# Arduino_MEGA2560_ref.net
KiCad netlist of a schematic drawn in EAGLE
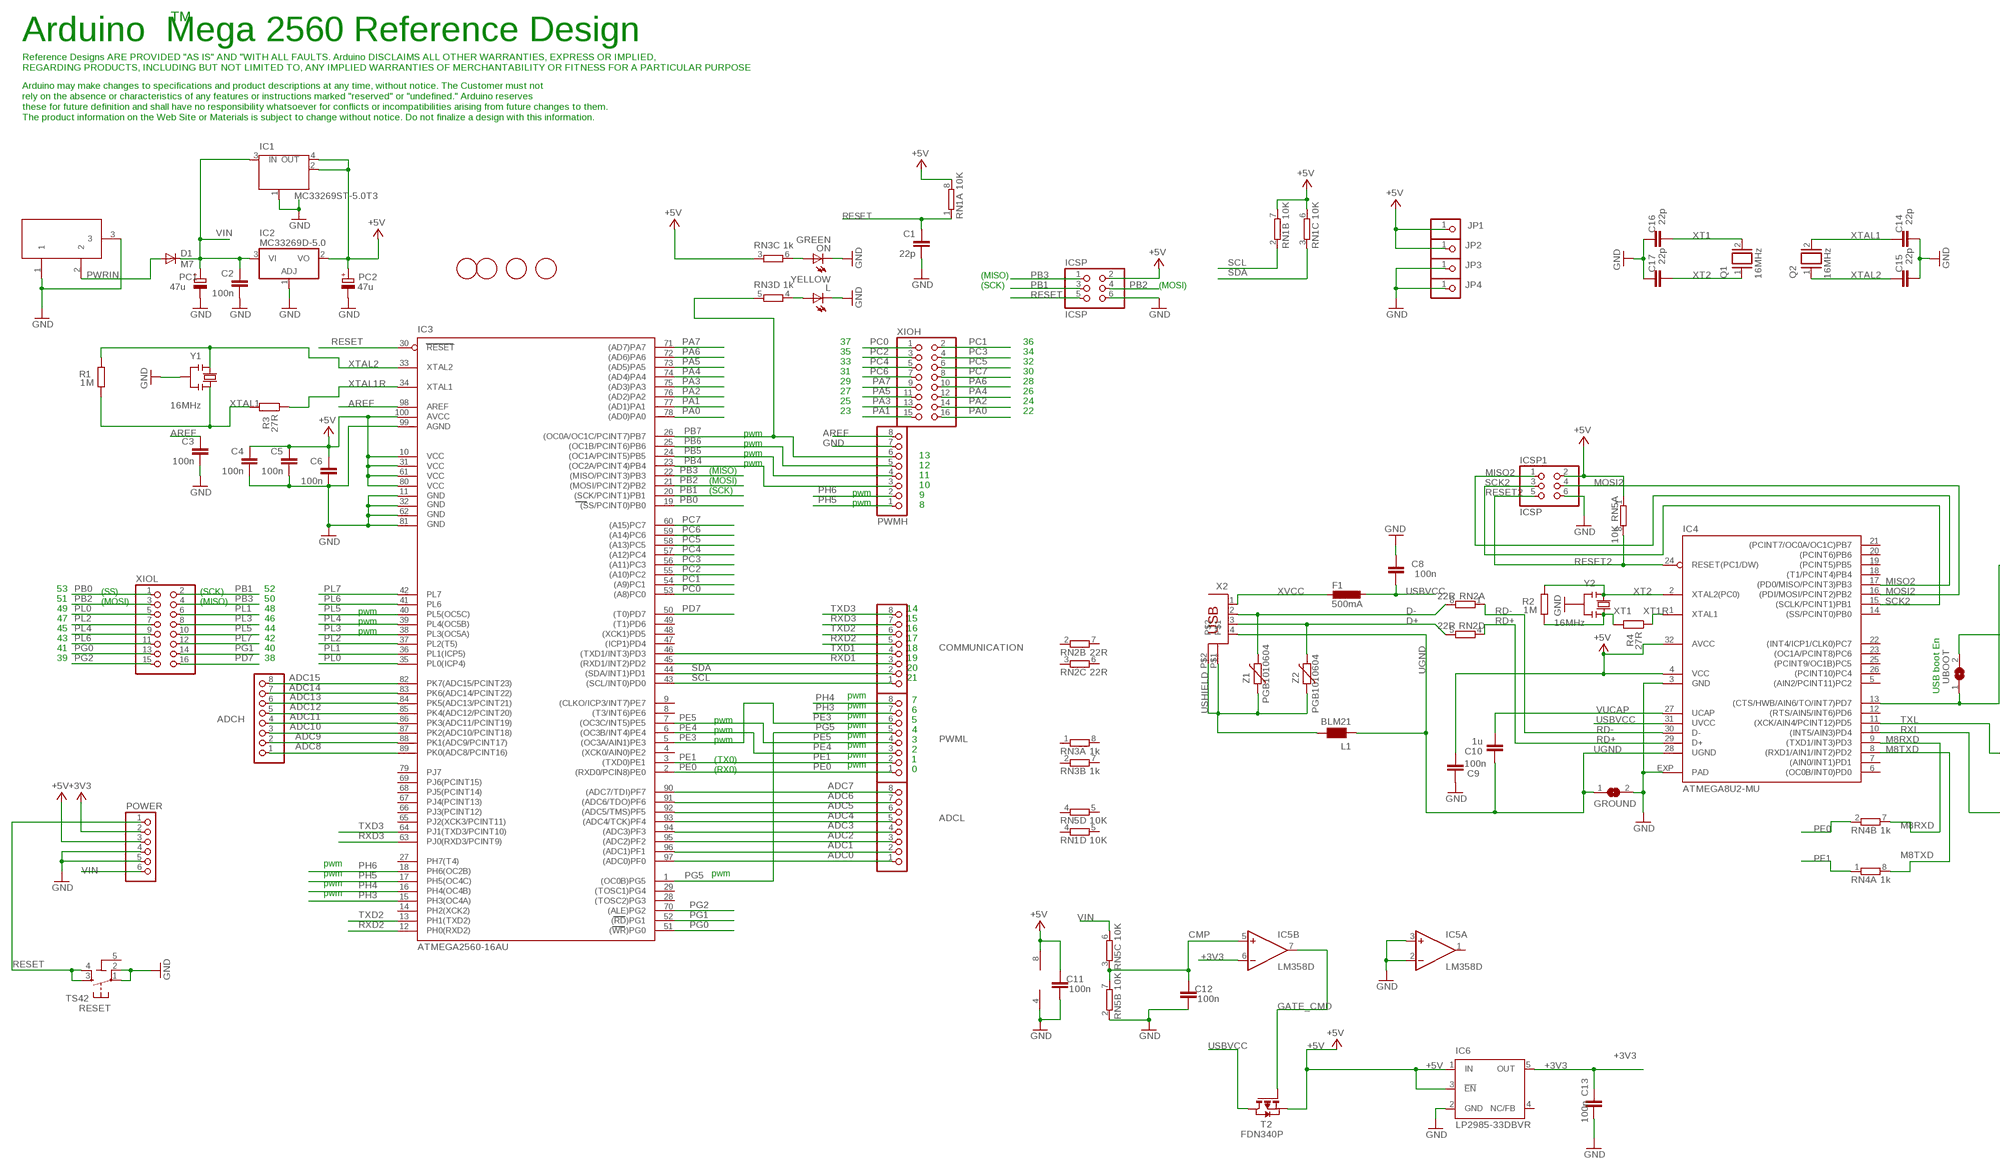
[diagram p0: schematic, sheet 1, part 1 of 2]
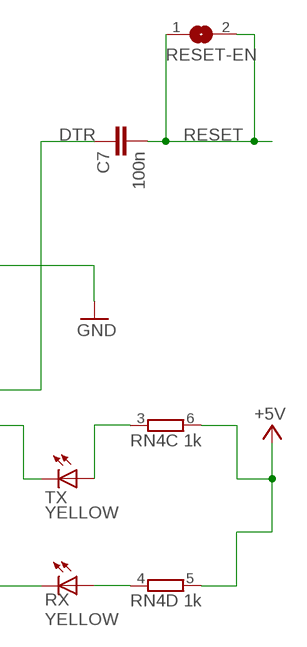
[diagram p1: schematic, sheet 1, part 2 of 2]

(export (version "E")
  (design (tool "Eeschema 10.0.6"))
  (components
    (comp (ref "ADCH")
      (value "PINHD-1X8")
      (footprint "eagle-import:1X08")
      (libsource (lib "eagle-import") (part "PINHD-1X8"))
    )
    (comp (ref "ADCL")
      (value "PINHD-1X8")
      (footprint "eagle-import:1X08")
      (libsource (lib "eagle-import") (part "PINHD-1X8"))
    )
    (comp (ref "C1")
      (value "22p")
      (footprint "eagle-import:C0603-ROUND")
      (libsource (lib "eagle-import") (part "C-EU0603-RND"))
    )
    (comp (ref "C2")
      (value "100n")
      (footprint "eagle-import:C0603-ROUND")
      (libsource (lib "eagle-import") (part "C-EU0603-RND"))
    )
    (comp (ref "C3")
      (value "100n")
      (footprint "eagle-import:C0603-ROUND")
      (libsource (lib "eagle-import") (part "C-EU0603-RND"))
    )
    (comp (ref "C4")
      (value "100n")
      (footprint "eagle-import:C0603-ROUND")
      (libsource (lib "eagle-import") (part "C-EU0603-RND"))
    )
    (comp (ref "C5")
      (value "100n")
      (footprint "eagle-import:C0603-ROUND")
      (libsource (lib "eagle-import") (part "C-EU0603-RND"))
    )
    (comp (ref "C6")
      (value "100n")
      (footprint "eagle-import:C0603-ROUND")
      (libsource (lib "eagle-import") (part "C-EU0603-RND"))
    )
    (comp (ref "C7")
      (value "100n")
      (footprint "eagle-import:C0603-ROUND")
      (libsource (lib "eagle-import") (part "C-EU0603-RND"))
    )
    (comp (ref "C8")
      (value "100n")
      (footprint "eagle-import:C0603")
      (libsource (lib "eagle-import") (part "rcl_C-EUC0603"))
    )
    (comp (ref "C9")
      (value "100n")
      (footprint "eagle-import:C0603-ROUND")
      (libsource (lib "eagle-import") (part "C-EU0603-RND"))
    )
    (comp (ref "C10")
      (value "1u")
      (footprint "eagle-import:C0603-ROUND")
      (libsource (lib "eagle-import") (part "C-EU0603-RND"))
    )
    (comp (ref "C11")
      (value "100n")
      (footprint "eagle-import:C0603")
      (libsource (lib "eagle-import") (part "rcl_C-EUC0603"))
    )
    (comp (ref "C12")
      (value "100n")
      (footprint "eagle-import:C0603-ROUND")
      (libsource (lib "eagle-import") (part "C-EU0603-RND"))
    )
    (comp (ref "C13")
      (value "100n")
      (footprint "eagle-import:C0603-ROUND")
      (libsource (lib "eagle-import") (part "C-EU0603-RND"))
    )
    (comp (ref "C14")
      (value "22p")
      (footprint "eagle-import:C0603-ROUND")
      (libsource (lib "eagle-import") (part "C-EU0603-RND"))
    )
    (comp (ref "C15")
      (value "22p")
      (footprint "eagle-import:C0603-ROUND")
      (libsource (lib "eagle-import") (part "C-EU0603-RND"))
    )
    (comp (ref "C16")
      (value "22p")
      (footprint "eagle-import:C0603-ROUND")
      (libsource (lib "eagle-import") (part "C-EU0603-RND"))
    )
    (comp (ref "C17")
      (value "22p")
      (footprint "eagle-import:C0603-ROUND")
      (libsource (lib "eagle-import") (part "C-EU0603-RND"))
    )
    (comp (ref "COMMUNICATION")
      (value "PINHD-1X8")
      (footprint "eagle-import:1X08")
      (libsource (lib "eagle-import") (part "PINHD-1X8"))
    )
    (comp (ref "D1")
      (value "M7")
      (footprint "eagle-import:SMB")
      (libsource (lib "eagle-import") (part "DIODE-SMB"))
    )
    (comp (ref "F1")
      (value "500mA")
      (footprint "eagle-import:L1812")
      (libsource (lib "eagle-import") (part "L-EUL1812"))
    )
    (comp (ref "GROUND")
      (value "SJ")
      (footprint "eagle-import:SJ")
      (libsource (lib "eagle-import") (part "SJ"))
    )
    (comp (ref "IC1")
      (value "MC33269ST-5.0T3")
      (footprint "eagle-import:SOT223")
      (libsource (lib "eagle-import") (part "MC33269ST-3.3T3"))
    )
    (comp (ref "IC2")
      (value "MC33269D-5.0")
      (footprint "eagle-import:DPACK")
      (libsource (lib "eagle-import") (part "MC33269?D-5.0"))
    )
    (comp (ref "IC3")
      (value "ATMEGA2560-16AU")
      (footprint "eagle-import:TQFP100")
      (libsource (lib "eagle-import") (part "ATMEGAAU1280-16"))
    )
    (comp (ref "IC4")
      (value "ATMEGA8U2-MU")
      (footprint "eagle-import:QFN32")
      (libsource (lib "eagle-import") (part "ATMEGA8U2-MU"))
    )
    (comp (ref "IC5")
      (value "LM358D")
      (footprint "eagle-import:SO08")
      (libsource (lib "eagle-import") (part "LM358D"))
    )
    (comp (ref "IC6")
      (value "LP2985-33DBVR")
      (footprint "eagle-import:SOT23-DBV")
      (libsource (lib "eagle-import") (part "TPS77033"))
    )
    (comp (ref "ICSP")
      (value "ICSP")
      (footprint "eagle-import:2X03")
      (libsource (lib "eagle-import") (part "PINHD-2X3"))
    )
    (comp (ref "ICSP1")
      (value "ICSP")
      (footprint "eagle-import:2X03")
      (libsource (lib "eagle-import") (part "PINHD-2X3"))
    )
    (comp (ref "JP1")
      (value "PINHD-1X1")
      (footprint "eagle-import:1X01")
      (libsource (lib "eagle-import") (part "PINHD-1X1"))
    )
    (comp (ref "JP2")
      (value "PINHD-1X1")
      (footprint "eagle-import:1X01")
      (libsource (lib "eagle-import") (part "PINHD-1X1"))
    )
    (comp (ref "JP3")
      (value "PINHD-1X1")
      (footprint "eagle-import:1X01")
      (libsource (lib "eagle-import") (part "PINHD-1X1"))
    )
    (comp (ref "JP4")
      (value "PINHD-1X1")
      (footprint "eagle-import:1X01")
      (libsource (lib "eagle-import") (part "PINHD-1X1"))
    )
    (comp (ref "L")
      (value "YELLOW")
      (footprint "eagle-import:CHIP-LED0805")
      (libsource (lib "eagle-import") (part "LEDCHIP-LED0805"))
    )
    (comp (ref "L1")
      (value "BLM21")
      (footprint "eagle-import:0805")
      (libsource (lib "eagle-import") (part "WE-CBF_0805"))
    )
    (comp (ref "ON")
      (value "GREEN")
      (footprint "eagle-import:CHIP-LED0805")
      (libsource (lib "eagle-import") (part "LEDCHIP-LED0805"))
    )
    (comp (ref "PC1")
      (value "47u")
      (footprint "eagle-import:PANASONIC_D")
      (libsource (lib "eagle-import") (part "CPOL-EUD"))
    )
    (comp (ref "PC2")
      (value "47u")
      (footprint "eagle-import:PANASONIC_D")
      (libsource (lib "eagle-import") (part "CPOL-EUD"))
    )
    (comp (ref "POWER")
      (value "PINHD-1X6")
      (footprint "eagle-import:1X06")
      (libsource (lib "eagle-import") (part "PINHD-1X6"))
    )
    (comp (ref "PWMH")
      (value "PINHD-1X8")
      (footprint "eagle-import:1X08")
      (libsource (lib "eagle-import") (part "PINHD-1X8"))
    )
    (comp (ref "PWML")
      (value "PINHD-1X8")
      (footprint "eagle-import:1X08")
      (libsource (lib "eagle-import") (part "PINHD-1X8"))
    )
    (comp (ref "Q1")
      (value "16MHz")
      (footprint "eagle-import:QS")
      (libsource (lib "eagle-import") (part "XTAL/S"))
    )
    (comp (ref "Q2")
      (value "16MHz")
      (footprint "eagle-import:QS")
      (libsource (lib "eagle-import") (part "XTAL/S"))
    )
    (comp (ref "R1")
      (value "1M")
      (footprint "eagle-import:R0603-ROUND")
      (libsource (lib "eagle-import") (part "R-EU_R0603"))
    )
    (comp (ref "R2")
      (value "1M")
      (footprint "eagle-import:R0603-ROUND")
      (libsource (lib "eagle-import") (part "R-EU_R0603"))
    )
    (comp (ref "R3")
      (value "27R")
      (footprint "eagle-import:R0603-ROUND")
      (libsource (lib "eagle-import") (part "R-EU_R0603"))
    )
    (comp (ref "R4")
      (value "27R")
      (footprint "eagle-import:R0603-ROUND")
      (libsource (lib "eagle-import") (part "R-EU_R0603"))
    )
    (comp (ref "RESET")
      (value "TS42")
      (footprint "eagle-import:TS42")
      (libsource (lib "eagle-import") (part "TS42"))
    )
    (comp (ref "RESET-EN")
      (value "SJ")
      (footprint "eagle-import:SJ")
      (libsource (lib "eagle-import") (part "SJ"))
    )
    (comp (ref "RN1")
      (value "10K")
      (footprint "eagle-import:CAT16")
      (libsource (lib "eagle-import") (part "4R-NCAT16"))
    )
    (comp (ref "RN2")
      (value "22R")
      (footprint "eagle-import:CAY16")
      (libsource (lib "eagle-import") (part "4R-NCAY16"))
    )
    (comp (ref "RN3")
      (value "1k")
      (footprint "eagle-import:CAY16")
      (libsource (lib "eagle-import") (part "4R-NCAY16"))
    )
    (comp (ref "RN4")
      (value "1k")
      (footprint "eagle-import:CAY16")
      (libsource (lib "eagle-import") (part "4R-NCAY16"))
    )
    (comp (ref "RN5")
      (value "10K")
      (footprint "eagle-import:CAT16")
      (libsource (lib "eagle-import") (part "4R-NCAT16"))
    )
    (comp (ref "RX")
      (value "YELLOW")
      (footprint "eagle-import:CHIP-LED0805")
      (libsource (lib "eagle-import") (part "LEDCHIP-LED0805"))
    )
    (comp (ref "T2")
      (value "FDN340P")
      (footprint "eagle-import:SOT-23")
      (libsource (lib "eagle-import") (part "PMOSSOT23"))
    )
    (comp (ref "TX")
      (value "YELLOW")
      (footprint "eagle-import:CHIP-LED0805")
      (libsource (lib "eagle-import") (part "LEDCHIP-LED0805"))
    )
    (comp (ref "U$2")
      (value "FIDUCIALMOUNT")
      (footprint "eagle-import:FIDUCIA-MOUNT")
      (libsource (lib "eagle-import") (part "FIDUCIALMOUNT"))
    )
    (comp (ref "U$3")
      (value "FIDUCIALMOUNT")
      (footprint "eagle-import:FIDUCIA-MOUNT")
      (libsource (lib "eagle-import") (part "FIDUCIALMOUNT"))
    )
    (comp (ref "U$4")
      (value "FIDUCIALMOUNT")
      (footprint "eagle-import:FIDUCIA-MOUNT")
      (libsource (lib "eagle-import") (part "FIDUCIALMOUNT"))
    )
    (comp (ref "U$5")
      (value "FIDUCIALMOUNT")
      (footprint "eagle-import:FIDUCIA-MOUNT")
      (libsource (lib "eagle-import") (part "FIDUCIALMOUNT"))
    )
    (comp (ref "UBOOT")
      (value "SJ")
      (footprint "eagle-import:SJ")
      (libsource (lib "eagle-import") (part "SJ"))
    )
    (comp (ref "X1")
      (value "DC21MMX")
      (footprint "eagle-import:DC-21MM")
      (libsource (lib "eagle-import") (part "DC21MMX"))
    )
    (comp (ref "X2")
      (value "PN61729")
      (footprint "eagle-import:PN61729")
      (libsource (lib "eagle-import") (part "PN61729"))
    )
    (comp (ref "XIOH")
      (value "PINHD-2X8")
      (footprint "eagle-import:2X08")
      (libsource (lib "eagle-import") (part "PINHD-2X8"))
    )
    (comp (ref "XIOL")
      (value "PINHD-2X8")
      (footprint "eagle-import:2X08")
      (libsource (lib "eagle-import") (part "PINHD-2X8"))
    )
    (comp (ref "Y1")
      (value "16MHz")
      (footprint "eagle-import:RESONATOR")
      (libsource (lib "eagle-import") (part "RESONATORMU"))
    )
    (comp (ref "Y2")
      (value "16MHz")
      (footprint "eagle-import:RESONATOR")
      (libsource (lib "eagle-import") (part "RESONATORMU"))
    )
    (comp (ref "Z1")
      (value "PGB1010604")
      (footprint "eagle-import:CT_CN0603")
      (libsource (lib "eagle-import") (part "VARISTORCN0603"))
    )
    (comp (ref "Z2")
      (value "PGB1010604")
      (footprint "eagle-import:CT_CN0603")
      (libsource (lib "eagle-import") (part "VARISTORCN0603"))
    )
  )
  (nets
    (net (code "1") (name "+3V3") (class "Default")
      (node (ref "C13") (pin "2") (pinfunction "2_2") (pintype "passive"))
      (node (ref "IC5") (pin "6") (pinfunction "-IN_6") (pintype "input"))
      (node (ref "IC6") (pin "5") (pinfunction "OUT_5") (pintype "passive"))
      (node (ref "POWER") (pin "2") (pinfunction "2_2") (pintype "passive"))
    )
    (net (code "2") (name "+5V") (class "Default")
      (node (ref "C11") (pin "2") (pinfunction "2_2") (pintype "passive"))
      (node (ref "C4") (pin "1") (pinfunction "1_1") (pintype "passive"))
      (node (ref "C5") (pin "1") (pinfunction "1_1") (pintype "passive"))
      (node (ref "C6") (pin "1") (pinfunction "1_1") (pintype "passive"))
      (node (ref "C9") (pin "1") (pinfunction "1_1") (pintype "passive"))
      (node (ref "IC1") (pin "2") (pinfunction "OUT_2") (pintype "passive"))
      (node (ref "IC1") (pin "4") (pinfunction "OUT_4") (pintype "passive"))
      (node (ref "IC2") (pin "2") (pinfunction "VO_2") (pintype "passive"))
      (node (ref "IC3") (pin "10") (pinfunction "VCC_10") (pintype "power_in"))
      (node (ref "IC3") (pin "100") (pinfunction "AVCC_100") (pintype "power_in"))
      (node (ref "IC3") (pin "31") (pinfunction "VCC1_31") (pintype "power_in"))
      (node (ref "IC3") (pin "61") (pinfunction "VCC2_61") (pintype "power_in"))
      (node (ref "IC3") (pin "80") (pinfunction "VCC3_80") (pintype "power_in"))
      (node (ref "IC4") (pin "32") (pinfunction "AVCC_32") (pintype "power_in"))
      (node (ref "IC4") (pin "4") (pinfunction "VCC_4") (pintype "power_in"))
      (node (ref "IC5") (pin "8") (pinfunction "V+_8") (pintype "power_in"))
      (node (ref "IC6") (pin "1") (pinfunction "IN_1") (pintype "input"))
      (node (ref "IC6") (pin "3") (pinfunction "~{EN}_3") (pintype "input"))
      (node (ref "ICSP") (pin "2") (pinfunction "2_2") (pintype "passive"))
      (node (ref "ICSP1") (pin "2") (pinfunction "2_2") (pintype "passive"))
      (node (ref "JP1") (pin "1") (pinfunction "1_1") (pintype "passive"))
      (node (ref "JP2") (pin "1") (pinfunction "1_1") (pintype "passive"))
      (node (ref "PC2") (pin "+") (pinfunction "+_+") (pintype "passive"))
      (node (ref "POWER") (pin "3") (pinfunction "3_3") (pintype "passive"))
      (node (ref "RN1") (pin "6") (pinfunction "2_6") (pintype "passive"))
      (node (ref "RN1") (pin "7") (pinfunction "2_7") (pintype "passive"))
      (node (ref "RN1") (pin "8") (pinfunction "2_8") (pintype "passive"))
      (node (ref "RN3") (pin "3") (pinfunction "1_3") (pintype "passive"))
      (node (ref "RN4") (pin "5") (pinfunction "2_5") (pintype "passive"))
      (node (ref "RN4") (pin "6") (pinfunction "2_6") (pintype "passive"))
      (node (ref "RN5") (pin "1") (pinfunction "1_1") (pintype "passive"))
      (node (ref "T2") (pin "2") (pinfunction "S_2") (pintype "passive"))
    )
    (net (code "3") (name "/5-GND") (class "Default")
      (node (ref "RESET") (pin "5") (pinfunction "5-GND_5") (pintype "power_in"))
    )
    (net (code "4") (name "/ADC0") (class "Default")
      (node (ref "ADCL") (pin "1") (pinfunction "1_1") (pintype "passive"))
      (node (ref "IC3") (pin "97") (pinfunction "(ADC0)PF0_97") (pintype "bidirectional"))
    )
    (net (code "5") (name "/ADC1") (class "Default")
      (node (ref "ADCL") (pin "2") (pinfunction "2_2") (pintype "passive"))
      (node (ref "IC3") (pin "96") (pinfunction "(ADC1)PF1_96") (pintype "bidirectional"))
    )
    (net (code "6") (name "/ADC2") (class "Default")
      (node (ref "ADCL") (pin "3") (pinfunction "3_3") (pintype "passive"))
      (node (ref "IC3") (pin "95") (pinfunction "(ADC2)PF2_95") (pintype "bidirectional"))
    )
    (net (code "7") (name "/ADC3") (class "Default")
      (node (ref "ADCL") (pin "4") (pinfunction "4_4") (pintype "passive"))
      (node (ref "IC3") (pin "94") (pinfunction "(ADC3)PF3_94") (pintype "bidirectional"))
    )
    (net (code "8") (name "/ADC4") (class "Default")
      (node (ref "ADCL") (pin "5") (pinfunction "5_5") (pintype "passive"))
      (node (ref "IC3") (pin "93") (pinfunction "(ADC4/TCK)PF4_93") (pintype "bidirectional"))
    )
    (net (code "9") (name "/ADC5") (class "Default")
      (node (ref "ADCL") (pin "6") (pinfunction "6_6") (pintype "passive"))
      (node (ref "IC3") (pin "92") (pinfunction "(ADC5/TMS)PF5_92") (pintype "bidirectional"))
    )
    (net (code "10") (name "/ADC6") (class "Default")
      (node (ref "ADCL") (pin "7") (pinfunction "7_7") (pintype "passive"))
      (node (ref "IC3") (pin "91") (pinfunction "(ADC6/TDO)PF6_91") (pintype "bidirectional"))
    )
    (net (code "11") (name "/ADC7") (class "Default")
      (node (ref "ADCL") (pin "8") (pinfunction "8_8") (pintype "passive"))
      (node (ref "IC3") (pin "90") (pinfunction "(ADC7/TDI)PF7_90") (pintype "bidirectional"))
    )
    (net (code "12") (name "/ADC8") (class "Default")
      (node (ref "ADCH") (pin "1") (pinfunction "1_1") (pintype "passive"))
      (node (ref "IC3") (pin "89") (pinfunction "PK0(ADC8/PCINT16)_89") (pintype "bidirectional"))
    )
    (net (code "13") (name "/ADC9") (class "Default")
      (node (ref "ADCH") (pin "2") (pinfunction "2_2") (pintype "passive"))
      (node (ref "IC3") (pin "88") (pinfunction "PK1(ADC9/PCINT17)_88") (pintype "bidirectional"))
    )
    (net (code "14") (name "/ADC10") (class "Default")
      (node (ref "ADCH") (pin "3") (pinfunction "3_3") (pintype "passive"))
      (node (ref "IC3") (pin "87") (pinfunction "PK2(ADC10/PCINT18)_87") (pintype "bidirectional"))
    )
    (net (code "15") (name "/ADC11") (class "Default")
      (node (ref "ADCH") (pin "4") (pinfunction "4_4") (pintype "passive"))
      (node (ref "IC3") (pin "86") (pinfunction "PK3(ADC11/PCINT19)_86") (pintype "bidirectional"))
    )
    (net (code "16") (name "/ADC12") (class "Default")
      (node (ref "ADCH") (pin "5") (pinfunction "5_5") (pintype "passive"))
      (node (ref "IC3") (pin "85") (pinfunction "PK4(ADC12/PCINT20)_85") (pintype "bidirectional"))
    )
    (net (code "17") (name "/ADC13") (class "Default")
      (node (ref "ADCH") (pin "6") (pinfunction "6_6") (pintype "passive"))
      (node (ref "IC3") (pin "84") (pinfunction "PK5(ADC13/PCINT21)_84") (pintype "bidirectional"))
    )
    (net (code "18") (name "/ADC14") (class "Default")
      (node (ref "ADCH") (pin "7") (pinfunction "7_7") (pintype "passive"))
      (node (ref "IC3") (pin "83") (pinfunction "PK6(ADC14/PCINT22)_83") (pintype "bidirectional"))
    )
    (net (code "19") (name "/ADC15") (class "Default")
      (node (ref "ADCH") (pin "8") (pinfunction "8_8") (pintype "passive"))
      (node (ref "IC3") (pin "82") (pinfunction "PK7(ADC15/PCINT23)_82") (pintype "bidirectional"))
    )
    (net (code "20") (name "/AREF") (class "Default")
      (node (ref "C3") (pin "1") (pinfunction "1_1") (pintype "passive"))
      (node (ref "IC3") (pin "98") (pinfunction "AREF_98") (pintype "bidirectional"))
      (node (ref "PWMH") (pin "8") (pinfunction "8_8") (pintype "passive"))
    )
    (net (code "21") (name "/CMP") (class "Default")
      (node (ref "C12") (pin "2") (pinfunction "2_2") (pintype "passive"))
      (node (ref "IC5") (pin "5") (pinfunction "+IN_5") (pintype "input"))
      (node (ref "RN5") (pin "3") (pinfunction "1_3") (pintype "passive"))
      (node (ref "RN5") (pin "7") (pinfunction "2_7") (pintype "passive"))
    )
    (net (code "22") (name "/D+") (class "Default")
      (node (ref "RN2") (pin "5") (pinfunction "2_5") (pintype "passive"))
      (node (ref "X2") (pin "3") (pinfunction "3_3") (pintype "bidirectional"))
      (node (ref "Z2") (pin "2") (pinfunction "2_2") (pintype "passive"))
    )
    (net (code "23") (name "/D-") (class "Default")
      (node (ref "RN2") (pin "8") (pinfunction "2_8") (pintype "passive"))
      (node (ref "X2") (pin "2") (pinfunction "2_2") (pintype "bidirectional"))
      (node (ref "Z1") (pin "2") (pinfunction "2_2") (pintype "passive"))
    )
    (net (code "24") (name "/DTR") (class "Default")
      (node (ref "C7") (pin "1") (pinfunction "1_1") (pintype "passive"))
      (node (ref "IC4") (pin "13") (pinfunction "(CTS/HWB/AIN6/TO/INT7)PD7_13") (pintype "bidirectional"))
      (node (ref "UBOOT") (pin "1") (pinfunction "1_1") (pintype "passive"))
    )
    (net (code "25") (name "/GATE_CMD") (class "Default")
      (node (ref "IC5") (pin "7") (pinfunction "OUT_7") (pintype "output"))
      (node (ref "T2") (pin "3") (pinfunction "G_3") (pintype "passive"))
    )
    (net (code "26") (name "/M8RXD") (class "Default")
      (node (ref "IC4") (pin "9") (pinfunction "(TXD1/INT3)PD3_9") (pintype "bidirectional"))
      (node (ref "RN4") (pin "7") (pinfunction "2_7") (pintype "passive"))
    )
    (net (code "27") (name "/M8TXD") (class "Default")
      (node (ref "IC4") (pin "8") (pinfunction "(RXD1/AIN1/INT2)PD2_8") (pintype "bidirectional"))
      (node (ref "RN4") (pin "8") (pinfunction "2_8") (pintype "passive"))
    )
    (net (code "28") (name "/MISO2") (class "Default")
      (node (ref "IC4") (pin "17") (pinfunction "(PD0/MISO/PCINT3)PB3_17") (pintype "bidirectional"))
      (node (ref "ICSP1") (pin "1") (pinfunction "1_1") (pintype "passive"))
    )
    (net (code "29") (name "/MOSI2") (class "Default")
      (node (ref "IC4") (pin "16") (pinfunction "(PDI/MOSI/PCINT2)PB2_16") (pintype "bidirectional"))
      (node (ref "ICSP1") (pin "4") (pinfunction "4_4") (pintype "passive"))
    )
    (net (code "30") (name "/PA0") (class "Default")
      (node (ref "IC3") (pin "78") (pinfunction "(AD0)PA0_78") (pintype "bidirectional"))
      (node (ref "XIOH") (pin "16") (pinfunction "16_16") (pintype "passive"))
    )
    (net (code "31") (name "/PA1") (class "Default")
      (node (ref "IC3") (pin "77") (pinfunction "(AD1)PA1_77") (pintype "bidirectional"))
      (node (ref "XIOH") (pin "15") (pinfunction "15_15") (pintype "passive"))
    )
    (net (code "32") (name "/PA2") (class "Default")
      (node (ref "IC3") (pin "76") (pinfunction "(AD2)PA2_76") (pintype "bidirectional"))
      (node (ref "XIOH") (pin "14") (pinfunction "14_14") (pintype "passive"))
    )
    (net (code "33") (name "/PA3") (class "Default")
      (node (ref "IC3") (pin "75") (pinfunction "(AD3)PA3_75") (pintype "bidirectional"))
      (node (ref "XIOH") (pin "13") (pinfunction "13_13") (pintype "passive"))
    )
    (net (code "34") (name "/PA4") (class "Default")
      (node (ref "IC3") (pin "74") (pinfunction "(AD4)PA4_74") (pintype "bidirectional"))
      (node (ref "XIOH") (pin "12") (pinfunction "12_12") (pintype "passive"))
    )
    (net (code "35") (name "/PA5") (class "Default")
      (node (ref "IC3") (pin "73") (pinfunction "(AD5)PA5_73") (pintype "bidirectional"))
      (node (ref "XIOH") (pin "11") (pinfunction "11_11") (pintype "passive"))
    )
    (net (code "36") (name "/PA6") (class "Default")
      (node (ref "IC3") (pin "72") (pinfunction "(AD6)PA6_72") (pintype "bidirectional"))
      (node (ref "XIOH") (pin "10") (pinfunction "10_10") (pintype "passive"))
    )
    (net (code "37") (name "/PA7") (class "Default")
      (node (ref "IC3") (pin "71") (pinfunction "(AD7)PA7_71") (pintype "bidirectional"))
      (node (ref "XIOH") (pin "9") (pinfunction "9_9") (pintype "passive"))
    )
    (net (code "38") (name "/PB0") (class "Default")
      (node (ref "IC3") (pin "19") (pinfunction "(SS/PCINT0)PB0_19") (pintype "bidirectional"))
      (node (ref "XIOL") (pin "1") (pinfunction "1_1") (pintype "passive"))
    )
    (net (code "39") (name "/PB1") (class "Default")
      (node (ref "IC3") (pin "20") (pinfunction "(SCK/PCINT1)PB1_20") (pintype "bidirectional"))
      (node (ref "ICSP") (pin "3") (pinfunction "3_3") (pintype "passive"))
      (node (ref "XIOL") (pin "2") (pinfunction "2_2") (pintype "passive"))
    )
    (net (code "40") (name "/PB2") (class "Default")
      (node (ref "IC3") (pin "21") (pinfunction "(MOSI/PCINT2)PB2_21") (pintype "bidirectional"))
      (node (ref "ICSP") (pin "4") (pinfunction "4_4") (pintype "passive"))
      (node (ref "XIOL") (pin "3") (pinfunction "3_3") (pintype "passive"))
    )
    (net (code "41") (name "/PB3") (class "Default")
      (node (ref "IC3") (pin "22") (pinfunction "(MISO/PCINT3)PB3_22") (pintype "bidirectional"))
      (node (ref "ICSP") (pin "1") (pinfunction "1_1") (pintype "passive"))
      (node (ref "XIOL") (pin "4") (pinfunction "4_4") (pintype "passive"))
    )
    (net (code "42") (name "/PB4") (class "Default")
      (node (ref "IC3") (pin "23") (pinfunction "(OC2A/PCINT4)PB4_23") (pintype "bidirectional"))
      (node (ref "PWMH") (pin "3") (pinfunction "3_3") (pintype "passive"))
    )
    (net (code "43") (name "/PB5") (class "Default")
      (node (ref "IC3") (pin "24") (pinfunction "(OC1A/PCINT5)PB5_24") (pintype "bidirectional"))
      (node (ref "PWMH") (pin "4") (pinfunction "4_4") (pintype "passive"))
    )
    (net (code "44") (name "/PB6") (class "Default")
      (node (ref "IC3") (pin "25") (pinfunction "(OC1B/PCINT6)PB6_25") (pintype "bidirectional"))
      (node (ref "PWMH") (pin "5") (pinfunction "5_5") (pintype "passive"))
    )
    (net (code "45") (name "/PB7") (class "Default")
      (node (ref "IC3") (pin "26") (pinfunction "(OC0A/OC1C/PCINT7)PB7_26") (pintype "bidirectional"))
      (node (ref "PWMH") (pin "6") (pinfunction "6_6") (pintype "passive"))
      (node (ref "RN3") (pin "5") (pinfunction "2_5") (pintype "passive"))
    )
    (net (code "46") (name "/PC0") (class "Default")
      (node (ref "IC3") (pin "53") (pinfunction "(A8)PC0_53") (pintype "bidirectional"))
      (node (ref "XIOH") (pin "1") (pinfunction "1_1") (pintype "passive"))
    )
    (net (code "47") (name "/PC1") (class "Default")
      (node (ref "IC3") (pin "54") (pinfunction "(A9)PC1_54") (pintype "bidirectional"))
      (node (ref "XIOH") (pin "2") (pinfunction "2_2") (pintype "passive"))
    )
    (net (code "48") (name "/PC2") (class "Default")
      (node (ref "IC3") (pin "55") (pinfunction "(A10)PC2_55") (pintype "bidirectional"))
      (node (ref "XIOH") (pin "3") (pinfunction "3_3") (pintype "passive"))
    )
    (net (code "49") (name "/PC3") (class "Default")
      (node (ref "IC3") (pin "56") (pinfunction "(A11)PC3_56") (pintype "bidirectional"))
      (node (ref "XIOH") (pin "4") (pinfunction "4_4") (pintype "passive"))
    )
    (net (code "50") (name "/PC4") (class "Default")
      (node (ref "IC3") (pin "57") (pinfunction "(A12)PC4_57") (pintype "bidirectional"))
      (node (ref "XIOH") (pin "5") (pinfunction "5_5") (pintype "passive"))
    )
    (net (code "51") (name "/PC5") (class "Default")
      (node (ref "IC3") (pin "58") (pinfunction "(A13)PC5_58") (pintype "bidirectional"))
      (node (ref "XIOH") (pin "6") (pinfunction "6_6") (pintype "passive"))
    )
    (net (code "52") (name "/PC6") (class "Default")
      (node (ref "IC3") (pin "59") (pinfunction "(A14)PC6_59") (pintype "bidirectional"))
      (node (ref "XIOH") (pin "7") (pinfunction "7_7") (pintype "passive"))
    )
    (net (code "53") (name "/PC7") (class "Default")
      (node (ref "IC3") (pin "60") (pinfunction "(A15)PC7_60") (pintype "bidirectional"))
      (node (ref "XIOH") (pin "8") (pinfunction "8_8") (pintype "passive"))
    )
    (net (code "54") (name "/PD7") (class "Default")
      (node (ref "IC3") (pin "50") (pinfunction "(T0)PD7_50") (pintype "bidirectional"))
      (node (ref "XIOL") (pin "16") (pinfunction "16_16") (pintype "passive"))
    )
    (net (code "55") (name "/PE0") (class "Default")
      (node (ref "IC3") (pin "2") (pinfunction "(RXD0/PCIN8)PE0_2") (pintype "bidirectional"))
      (node (ref "PWML") (pin "1") (pinfunction "1_1") (pintype "passive"))
      (node (ref "RN4") (pin "2") (pinfunction "1_2") (pintype "passive"))
    )
    (net (code "56") (name "/PE1") (class "Default")
      (node (ref "IC3") (pin "3") (pinfunction "(TXD0)PE1_3") (pintype "bidirectional"))
      (node (ref "PWML") (pin "2") (pinfunction "2_2") (pintype "passive"))
      (node (ref "RN4") (pin "1") (pinfunction "1_1") (pintype "passive"))
    )
    (net (code "57") (name "/PE3") (class "Default")
      (node (ref "IC3") (pin "5") (pinfunction "(OC3A/AIN1)PE3_5") (pintype "bidirectional"))
      (node (ref "PWML") (pin "6") (pinfunction "6_6") (pintype "passive"))
    )
    (net (code "58") (name "/PE4") (class "Default")
      (node (ref "IC3") (pin "6") (pinfunction "(OC3B/INT4)PE4_6") (pintype "bidirectional"))
      (node (ref "PWML") (pin "3") (pinfunction "3_3") (pintype "passive"))
    )
    (net (code "59") (name "/PE5") (class "Default")
      (node (ref "IC3") (pin "7") (pinfunction "(OC3C/INT5)PE5_7") (pintype "bidirectional"))
      (node (ref "PWML") (pin "4") (pinfunction "4_4") (pintype "passive"))
    )
    (net (code "60") (name "/PG0") (class "Default")
      (node (ref "IC3") (pin "51") (pinfunction "(WR)PG0_51") (pintype "bidirectional"))
      (node (ref "XIOL") (pin "13") (pinfunction "13_13") (pintype "passive"))
    )
    (net (code "61") (name "/PG1") (class "Default")
      (node (ref "IC3") (pin "52") (pinfunction "(RD)PG1_52") (pintype "bidirectional"))
      (node (ref "XIOL") (pin "14") (pinfunction "14_14") (pintype "passive"))
    )
    (net (code "62") (name "/PG2") (class "Default")
      (node (ref "IC3") (pin "70") (pinfunction "(ALE)PG2_70") (pintype "bidirectional"))
      (node (ref "XIOL") (pin "15") (pinfunction "15_15") (pintype "passive"))
    )
    (net (code "63") (name "/PG5") (class "Default")
      (node (ref "IC3") (pin "1") (pinfunction "(OC0B)PG5_1") (pintype "bidirectional"))
      (node (ref "PWML") (pin "5") (pinfunction "5_5") (pintype "passive"))
    )
    (net (code "64") (name "/PH3") (class "Default")
      (node (ref "IC3") (pin "15") (pinfunction "PH3(OC4A)_15") (pintype "bidirectional"))
      (node (ref "PWML") (pin "7") (pinfunction "7_7") (pintype "passive"))
    )
    (net (code "65") (name "/PH4") (class "Default")
      (node (ref "IC3") (pin "16") (pinfunction "PH4(OC4B)_16") (pintype "bidirectional"))
      (node (ref "PWML") (pin "8") (pinfunction "8_8") (pintype "passive"))
    )
    (net (code "66") (name "/PH5") (class "Default")
      (node (ref "IC3") (pin "17") (pinfunction "PH5(OC4C)_17") (pintype "bidirectional"))
      (node (ref "PWMH") (pin "1") (pinfunction "1_1") (pintype "passive"))
    )
    (net (code "67") (name "/PH6") (class "Default")
      (node (ref "IC3") (pin "18") (pinfunction "PH6(OC2B)_18") (pintype "bidirectional"))
      (node (ref "PWMH") (pin "2") (pinfunction "2_2") (pintype "passive"))
    )
    (net (code "68") (name "/PL0") (class "Default")
      (node (ref "IC3") (pin "35") (pinfunction "PL0(ICP4)_35") (pintype "bidirectional"))
      (node (ref "XIOL") (pin "5") (pinfunction "5_5") (pintype "passive"))
    )
    (net (code "69") (name "/PL1") (class "Default")
      (node (ref "IC3") (pin "36") (pinfunction "PL1(ICP5)_36") (pintype "bidirectional"))
      (node (ref "XIOL") (pin "6") (pinfunction "6_6") (pintype "passive"))
    )
    (net (code "70") (name "/PL2") (class "Default")
      (node (ref "IC3") (pin "37") (pinfunction "PL2(T5)_37") (pintype "bidirectional"))
      (node (ref "XIOL") (pin "7") (pinfunction "7_7") (pintype "passive"))
    )
    (net (code "71") (name "/PL3") (class "Default")
      (node (ref "IC3") (pin "38") (pinfunction "PL3(OC5A)_38") (pintype "bidirectional"))
      (node (ref "XIOL") (pin "8") (pinfunction "8_8") (pintype "passive"))
    )
    (net (code "72") (name "/PL4") (class "Default")
      (node (ref "IC3") (pin "39") (pinfunction "PL4(OC5B)_39") (pintype "bidirectional"))
      (node (ref "XIOL") (pin "9") (pinfunction "9_9") (pintype "passive"))
    )
    (net (code "73") (name "/PL5") (class "Default")
      (node (ref "IC3") (pin "40") (pinfunction "PL5(OC5C)_40") (pintype "bidirectional"))
      (node (ref "XIOL") (pin "10") (pinfunction "10_10") (pintype "passive"))
    )
    (net (code "74") (name "/PL6") (class "Default")
      (node (ref "IC3") (pin "41") (pinfunction "PL6_41") (pintype "bidirectional"))
      (node (ref "XIOL") (pin "11") (pinfunction "11_11") (pintype "passive"))
    )
    (net (code "75") (name "/PL7") (class "Default")
      (node (ref "IC3") (pin "42") (pinfunction "PL7_42") (pintype "bidirectional"))
      (node (ref "XIOL") (pin "12") (pinfunction "12_12") (pintype "passive"))
    )
    (net (code "76") (name "/PWRIN") (class "Default")
      (node (ref "D1") (pin "A") (pinfunction "A_A") (pintype "passive"))
      (node (ref "X1") (pin "2") (pinfunction "2_2") (pintype "power_in"))
    )
    (net (code "77") (name "/RD+") (class "Default")
      (node (ref "IC4") (pin "29") (pinfunction "D+_29") (pintype "bidirectional"))
      (node (ref "RN2") (pin "4") (pinfunction "1_4") (pintype "passive"))
    )
    (net (code "78") (name "/RD-") (class "Default")
      (node (ref "IC4") (pin "30") (pinfunction "D-_30") (pintype "bidirectional"))
      (node (ref "RN2") (pin "1") (pinfunction "1_1") (pintype "passive"))
    )
    (net (code "79") (name "/RESET") (class "Default")
      (node (ref "C1") (pin "1") (pinfunction "1_1") (pintype "passive"))
      (node (ref "C7") (pin "2") (pinfunction "2_2") (pintype "passive"))
      (node (ref "IC3") (pin "30") (pinfunction "RESET_30") (pintype "input"))
      (node (ref "ICSP") (pin "5") (pinfunction "5_5") (pintype "passive"))
      (node (ref "POWER") (pin "1") (pinfunction "1_1") (pintype "passive"))
      (node (ref "RESET") (pin "3") (pinfunction "3_3") (pintype "passive"))
      (node (ref "RESET") (pin "4") (pinfunction "4_4") (pintype "passive"))
      (node (ref "RESET-EN") (pin "1") (pinfunction "1_1") (pintype "passive"))
      (node (ref "RESET-EN") (pin "2") (pinfunction "2_2") (pintype "passive"))
      (node (ref "RN1") (pin "1") (pinfunction "1_1") (pintype "passive"))
    )
    (net (code "80") (name "/RESET2") (class "Default")
      (node (ref "IC4") (pin "24") (pinfunction "RESET(PC1/DW)_24") (pintype "input"))
      (node (ref "ICSP1") (pin "5") (pinfunction "5_5") (pintype "passive"))
      (node (ref "RN5") (pin "8") (pinfunction "2_8") (pintype "passive"))
    )
    (net (code "81") (name "/RXD1") (class "Default")
      (node (ref "COMMUNICATION") (pin "3") (pinfunction "3_3") (pintype "passive"))
      (node (ref "IC3") (pin "45") (pinfunction "(RXD1/INT2)PD2_45") (pintype "bidirectional"))
    )
    (net (code "82") (name "/RXD2") (class "Default")
      (node (ref "COMMUNICATION") (pin "5") (pinfunction "5_5") (pintype "passive"))
      (node (ref "IC3") (pin "12") (pinfunction "PH0(RXD2)_12") (pintype "bidirectional"))
    )
    (net (code "83") (name "/RXD3") (class "Default")
      (node (ref "COMMUNICATION") (pin "7") (pinfunction "7_7") (pintype "passive"))
      (node (ref "IC3") (pin "63") (pinfunction "PJ0(RXD3/PCINT9)_63") (pintype "bidirectional"))
    )
    (net (code "84") (name "/RXL") (class "Default")
      (node (ref "IC4") (pin "10") (pinfunction "(INT5/AIN3)PD4_10") (pintype "bidirectional"))
      (node (ref "RX") (pin "C") (pinfunction "C_C") (pintype "passive"))
    )
    (net (code "85") (name "/SCK2") (class "Default")
      (node (ref "IC4") (pin "15") (pinfunction "(SCLK/PCINT1)PB1_15") (pintype "bidirectional"))
      (node (ref "ICSP1") (pin "3") (pinfunction "3_3") (pintype "passive"))
    )
    (net (code "86") (name "/SCL") (class "Default")
      (node (ref "COMMUNICATION") (pin "1") (pinfunction "1_1") (pintype "passive"))
      (node (ref "IC3") (pin "43") (pinfunction "(SCL/INT0)PD0_43") (pintype "bidirectional"))
      (node (ref "RN1") (pin "2") (pinfunction "1_2") (pintype "passive"))
    )
    (net (code "87") (name "/SDA") (class "Default")
      (node (ref "COMMUNICATION") (pin "2") (pinfunction "2_2") (pintype "passive"))
      (node (ref "IC3") (pin "44") (pinfunction "(SDA/INT1)PD1_44") (pintype "bidirectional"))
      (node (ref "RN1") (pin "3") (pinfunction "1_3") (pintype "passive"))
    )
    (net (code "88") (name "/TXD1") (class "Default")
      (node (ref "COMMUNICATION") (pin "4") (pinfunction "4_4") (pintype "passive"))
      (node (ref "IC3") (pin "46") (pinfunction "(TXD1/INT3)PD3_46") (pintype "bidirectional"))
    )
    (net (code "89") (name "/TXD2") (class "Default")
      (node (ref "COMMUNICATION") (pin "6") (pinfunction "6_6") (pintype "passive"))
      (node (ref "IC3") (pin "13") (pinfunction "PH1(TXD2)_13") (pintype "bidirectional"))
    )
    (net (code "90") (name "/TXD3") (class "Default")
      (node (ref "COMMUNICATION") (pin "8") (pinfunction "8_8") (pintype "passive"))
      (node (ref "IC3") (pin "64") (pinfunction "PJ1(TXD3/PCINT10)_64") (pintype "bidirectional"))
    )
    (net (code "91") (name "/TXL") (class "Default")
      (node (ref "IC4") (pin "11") (pinfunction "(XCK/AIN4/PCINT12)PD5_11") (pintype "bidirectional"))
      (node (ref "TX") (pin "C") (pinfunction "C_C") (pintype "passive"))
    )
    (net (code "92") (name "/UGND") (class "Default")
      (node (ref "C10") (pin "2") (pinfunction "2_2") (pintype "passive"))
      (node (ref "GROUND") (pin "1") (pinfunction "1_1") (pintype "passive"))
      (node (ref "IC4") (pin "28") (pinfunction "UGND_28") (pintype "power_in"))
      (node (ref "L1") (pin "1") (pinfunction "1_1") (pintype "passive"))
      (node (ref "X2") (pin "4") (pinfunction "4_4") (pintype "bidirectional"))
    )
    (net (code "93") (name "/USBVCC") (class "Default")
      (node (ref "C8") (pin "1") (pinfunction "1_1") (pintype "passive"))
      (node (ref "F1") (pin "1") (pinfunction "1_1") (pintype "passive"))
      (node (ref "IC4") (pin "31") (pinfunction "UVCC_31") (pintype "power_in"))
      (node (ref "T2") (pin "1") (pinfunction "D_1") (pintype "passive"))
    )
    (net (code "94") (name "/USHIELD") (class "Default")
      (node (ref "L1") (pin "2") (pinfunction "2_2") (pintype "passive"))
      (node (ref "X2") (pin "P$1") (pinfunction "P$1_P$1") (pintype "bidirectional"))
      (node (ref "X2") (pin "P$2") (pinfunction "P$2_P$2") (pintype "bidirectional"))
      (node (ref "Z1") (pin "1") (pinfunction "1_1") (pintype "passive"))
      (node (ref "Z2") (pin "1") (pinfunction "1_1") (pintype "passive"))
    )
    (net (code "95") (name "/VIN") (class "Default")
      (node (ref "C2") (pin "1") (pinfunction "1_1") (pintype "passive"))
      (node (ref "D1") (pin "C") (pinfunction "C_C") (pintype "passive"))
      (node (ref "IC1") (pin "3") (pinfunction "IN_3") (pintype "input"))
      (node (ref "IC2") (pin "3") (pinfunction "VI_3") (pintype "input"))
      (node (ref "PC1") (pin "+") (pinfunction "+_+") (pintype "passive"))
      (node (ref "POWER") (pin "6") (pinfunction "6_6") (pintype "passive"))
      (node (ref "RN5") (pin "6") (pinfunction "2_6") (pintype "passive"))
    )
    (net (code "96") (name "/VUCAP") (class "Default")
      (node (ref "C10") (pin "1") (pinfunction "1_1") (pintype "passive"))
      (node (ref "IC4") (pin "27") (pinfunction "UCAP_27") (pintype "passive"))
    )
    (net (code "97") (name "/XT1") (class "Default")
      (node (ref "C16") (pin "1") (pinfunction "1_1") (pintype "passive"))
      (node (ref "Q1") (pin "2") (pinfunction "2_2") (pintype "passive"))
      (node (ref "R2") (pin "1") (pinfunction "1_1") (pintype "passive"))
      (node (ref "R4") (pin "2") (pinfunction "2_2") (pintype "passive"))
      (node (ref "Y2") (pin "3") (pinfunction "3_3") (pintype "passive"))
    )
    (net (code "98") (name "/XT1R") (class "Default")
      (node (ref "IC4") (pin "1") (pinfunction "XTAL1_1") (pintype "bidirectional"))
      (node (ref "R4") (pin "1") (pinfunction "1_1") (pintype "passive"))
    )
    (net (code "99") (name "/XT2") (class "Default")
      (node (ref "C17") (pin "1") (pinfunction "1_1") (pintype "passive"))
      (node (ref "IC4") (pin "2") (pinfunction "XTAL2(PC0)_2") (pintype "bidirectional"))
      (node (ref "Q1") (pin "1") (pinfunction "1_1") (pintype "passive"))
      (node (ref "R2") (pin "2") (pinfunction "2_2") (pintype "passive"))
      (node (ref "Y2") (pin "1") (pinfunction "1_1") (pintype "passive"))
    )
    (net (code "100") (name "/XTAL1") (class "Default")
      (node (ref "C14") (pin "2") (pinfunction "2_2") (pintype "passive"))
      (node (ref "Q2") (pin "2") (pinfunction "2_2") (pintype "passive"))
      (node (ref "R1") (pin "1") (pinfunction "1_1") (pintype "passive"))
      (node (ref "R3") (pin "2") (pinfunction "2_2") (pintype "passive"))
      (node (ref "Y1") (pin "3") (pinfunction "3_3") (pintype "passive"))
    )
    (net (code "101") (name "/XTAL1R") (class "Default")
      (node (ref "IC3") (pin "34") (pinfunction "XTAL1_34") (pintype "input"))
      (node (ref "R3") (pin "1") (pinfunction "1_1") (pintype "passive"))
    )
    (net (code "102") (name "/XTAL2") (class "Default")
      (node (ref "C15") (pin "2") (pinfunction "2_2") (pintype "passive"))
      (node (ref "IC3") (pin "33") (pinfunction "XTAL2_33") (pintype "output"))
      (node (ref "Q2") (pin "1") (pinfunction "1_1") (pintype "passive"))
      (node (ref "R1") (pin "2") (pinfunction "2_2") (pintype "passive"))
      (node (ref "Y1") (pin "1") (pinfunction "1_1") (pintype "passive"))
    )
    (net (code "103") (name "/XVCC") (class "Default")
      (node (ref "F1") (pin "2") (pinfunction "2_2") (pintype "passive"))
      (node (ref "X2") (pin "1") (pinfunction "1_1") (pintype "bidirectional"))
    )
    (net (code "104") (name "GND") (class "Default")
      (node (ref "C1") (pin "2") (pinfunction "2_2") (pintype "passive"))
      (node (ref "C11") (pin "1") (pinfunction "1_1") (pintype "passive"))
      (node (ref "C12") (pin "1") (pinfunction "1_1") (pintype "passive"))
      (node (ref "C13") (pin "1") (pinfunction "1_1") (pintype "passive"))
      (node (ref "C14") (pin "1") (pinfunction "1_1") (pintype "passive"))
      (node (ref "C15") (pin "1") (pinfunction "1_1") (pintype "passive"))
      (node (ref "C16") (pin "2") (pinfunction "2_2") (pintype "passive"))
      (node (ref "C17") (pin "2") (pinfunction "2_2") (pintype "passive"))
      (node (ref "C2") (pin "2") (pinfunction "2_2") (pintype "passive"))
      (node (ref "C3") (pin "2") (pinfunction "2_2") (pintype "passive"))
      (node (ref "C4") (pin "2") (pinfunction "2_2") (pintype "passive"))
      (node (ref "C5") (pin "2") (pinfunction "2_2") (pintype "passive"))
      (node (ref "C6") (pin "2") (pinfunction "2_2") (pintype "passive"))
      (node (ref "C8") (pin "2") (pinfunction "2_2") (pintype "passive"))
      (node (ref "C9") (pin "2") (pinfunction "2_2") (pintype "passive"))
      (node (ref "GROUND") (pin "2") (pinfunction "2_2") (pintype "passive"))
      (node (ref "IC1") (pin "1") (pinfunction "GND/ADJ_1") (pintype "input"))
      (node (ref "IC2") (pin "1") (pinfunction "ADJ_1") (pintype "input"))
      (node (ref "IC3") (pin "11") (pinfunction "GND_11") (pintype "power_in"))
      (node (ref "IC3") (pin "32") (pinfunction "GND1_32") (pintype "power_in"))
      (node (ref "IC3") (pin "62") (pinfunction "GND2_62") (pintype "power_in"))
      (node (ref "IC3") (pin "81") (pinfunction "GND3_81") (pintype "power_in"))
      (node (ref "IC3") (pin "99") (pinfunction "AGND_99") (pintype "power_in"))
      (node (ref "IC4") (pin "3") (pinfunction "GND_3") (pintype "power_in"))
      (node (ref "IC4") (pin "EXP") (pinfunction "PAD_EXP") (pintype "power_in"))
      (node (ref "IC5") (pin "2") (pinfunction "-IN_2") (pintype "input"))
      (node (ref "IC5") (pin "3") (pinfunction "+IN_3") (pintype "input"))
      (node (ref "IC5") (pin "4") (pinfunction "V-_4") (pintype "power_in"))
      (node (ref "IC6") (pin "2") (pinfunction "GND_2") (pintype "power_in"))
      (node (ref "ICSP") (pin "6") (pinfunction "6_6") (pintype "passive"))
      (node (ref "ICSP1") (pin "6") (pinfunction "6_6") (pintype "passive"))
      (node (ref "JP3") (pin "1") (pinfunction "1_1") (pintype "passive"))
      (node (ref "JP4") (pin "1") (pinfunction "1_1") (pintype "passive"))
      (node (ref "L") (pin "C") (pinfunction "C_C") (pintype "passive"))
      (node (ref "ON") (pin "C") (pinfunction "C_C") (pintype "passive"))
      (node (ref "PC1") (pin "-") (pinfunction "-_-") (pintype "passive"))
      (node (ref "PC2") (pin "-") (pinfunction "-_-") (pintype "passive"))
      (node (ref "POWER") (pin "4") (pinfunction "4_4") (pintype "passive"))
      (node (ref "POWER") (pin "5") (pinfunction "5_5") (pintype "passive"))
      (node (ref "PWMH") (pin "7") (pinfunction "7_7") (pintype "passive"))
      (node (ref "RESET") (pin "1") (pinfunction "1_1") (pintype "passive"))
      (node (ref "RESET") (pin "2") (pinfunction "2_2") (pintype "passive"))
      (node (ref "RN5") (pin "2") (pinfunction "1_2") (pintype "passive"))
      (node (ref "UBOOT") (pin "2") (pinfunction "2_2") (pintype "passive"))
      (node (ref "X1") (pin "1") (pinfunction "1_1") (pintype "power_in"))
      (node (ref "X1") (pin "3") (pinfunction "3_3") (pintype "power_in"))
      (node (ref "Y1") (pin "2") (pinfunction "2_2") (pintype "passive"))
      (node (ref "Y2") (pin "2") (pinfunction "2_2") (pintype "passive"))
    )
    (net (code "105") (name "Net-(RN3C-2)") (class "Default")
      (node (ref "ON") (pin "A") (pinfunction "A_A") (pintype "passive"))
      (node (ref "RN3") (pin "6") (pinfunction "2_6") (pintype "passive"))
    )
    (net (code "106") (name "Net-(RN3D-1)") (class "Default")
      (node (ref "L") (pin "A") (pinfunction "A_A") (pintype "passive"))
      (node (ref "RN3") (pin "4") (pinfunction "1_4") (pintype "passive"))
    )
    (net (code "107") (name "Net-(RN4C-1)") (class "Default")
      (node (ref "RN4") (pin "3") (pinfunction "1_3") (pintype "passive"))
      (node (ref "TX") (pin "A") (pinfunction "A_A") (pintype "passive"))
    )
    (net (code "108") (name "Net-(RN4D-1)") (class "Default")
      (node (ref "RN4") (pin "4") (pinfunction "1_4") (pintype "passive"))
      (node (ref "RX") (pin "A") (pinfunction "A_A") (pintype "passive"))
    )
    (net (code "109") (name "unconnected-(IC3-(CLKO{slash}ICP3{slash}INT7)PE7-Pad9)") (class "Default")
      (node (ref "IC3") (pin "9") (pinfunction "(CLKO/ICP3/INT7)PE7_9") (pintype "bidirectional"))
    )
    (net (code "110") (name "unconnected-(IC3-(ICP1)PD4-Pad47)") (class "Default")
      (node (ref "IC3") (pin "47") (pinfunction "(ICP1)PD4_47") (pintype "bidirectional"))
    )
    (net (code "111") (name "unconnected-(IC3-(T1)PD6-Pad49)") (class "Default")
      (node (ref "IC3") (pin "49") (pinfunction "(T1)PD6_49") (pintype "bidirectional"))
    )
    (net (code "112") (name "unconnected-(IC3-(T3{slash}INT6)PE6-Pad8)") (class "Default")
      (node (ref "IC3") (pin "8") (pinfunction "(T3/INT6)PE6_8") (pintype "bidirectional"))
    )
    (net (code "113") (name "unconnected-(IC3-(TOSC1)PG4-Pad29)") (class "Default")
      (node (ref "IC3") (pin "29") (pinfunction "(TOSC1)PG4_29") (pintype "bidirectional"))
    )
    (net (code "114") (name "unconnected-(IC3-(TOSC2)PG3-Pad28)") (class "Default")
      (node (ref "IC3") (pin "28") (pinfunction "(TOSC2)PG3_28") (pintype "bidirectional"))
    )
    (net (code "115") (name "unconnected-(IC3-(XCK0{slash}AIN0)PE2-Pad4)") (class "Default")
      (node (ref "IC3") (pin "4") (pinfunction "(XCK0/AIN0)PE2_4") (pintype "bidirectional"))
    )
    (net (code "116") (name "unconnected-(IC3-(XCK1)PD5-Pad48)") (class "Default")
      (node (ref "IC3") (pin "48") (pinfunction "(XCK1)PD5_48") (pintype "bidirectional"))
    )
    (net (code "117") (name "unconnected-(IC3-PH2(XCK2)-Pad14)") (class "Default")
      (node (ref "IC3") (pin "14") (pinfunction "PH2(XCK2)_14") (pintype "bidirectional"))
    )
    (net (code "118") (name "unconnected-(IC3-PH7(T4)-Pad27)") (class "Default")
      (node (ref "IC3") (pin "27") (pinfunction "PH7(T4)_27") (pintype "bidirectional"))
    )
    (net (code "119") (name "unconnected-(IC3-PJ2(XCK3{slash}PCINT11)-Pad65)") (class "Default")
      (node (ref "IC3") (pin "65") (pinfunction "PJ2(XCK3/PCINT11)_65") (pintype "bidirectional"))
    )
    (net (code "120") (name "unconnected-(IC3-PJ3(PCINT12)-Pad66)") (class "Default")
      (node (ref "IC3") (pin "66") (pinfunction "PJ3(PCINT12)_66") (pintype "bidirectional"))
    )
    (net (code "121") (name "unconnected-(IC3-PJ4(PCINT13)-Pad67)") (class "Default")
      (node (ref "IC3") (pin "67") (pinfunction "PJ4(PCINT13)_67") (pintype "bidirectional"))
    )
    (net (code "122") (name "unconnected-(IC3-PJ5(PCINT14)-Pad68)") (class "Default")
      (node (ref "IC3") (pin "68") (pinfunction "PJ5(PCINT14)_68") (pintype "bidirectional"))
    )
    (net (code "123") (name "unconnected-(IC3-PJ6(PCINT15)-Pad69)") (class "Default")
      (node (ref "IC3") (pin "69") (pinfunction "PJ6(PCINT15)_69") (pintype "bidirectional"))
    )
    (net (code "124") (name "unconnected-(IC3-PJ7-Pad79)") (class "Default")
      (node (ref "IC3") (pin "79") (pinfunction "PJ7_79") (pintype "bidirectional"))
    )
    (net (code "125") (name "unconnected-(IC4-(AIN0{slash}INT1)PD1-Pad7)") (class "Default")
      (node (ref "IC4") (pin "7") (pinfunction "(AIN0/INT1)PD1_7") (pintype "bidirectional"))
    )
    (net (code "126") (name "unconnected-(IC4-(AIN2{slash}PCINT11)PC2-Pad5)") (class "Default")
      (node (ref "IC4") (pin "5") (pinfunction "(AIN2/PCINT11)PC2_5") (pintype "bidirectional"))
    )
    (net (code "127") (name "unconnected-(IC4-(INT4{slash}ICP1{slash}CLK0)PC7-Pad22)") (class "Default")
      (node (ref "IC4") (pin "22") (pinfunction "(INT4/ICP1/CLK0)PC7_22") (pintype "bidirectional"))
    )
    (net (code "128") (name "unconnected-(IC4-(OC0B{slash}INT0)PD0-Pad6)") (class "Default")
      (node (ref "IC4") (pin "6") (pinfunction "(OC0B/INT0)PD0_6") (pintype "bidirectional"))
    )
    (net (code "129") (name "unconnected-(IC4-(OC1A{slash}PCINT8)PC6-Pad23)") (class "Default")
      (node (ref "IC4") (pin "23") (pinfunction "(OC1A/PCINT8)PC6_23") (pintype "bidirectional"))
    )
    (net (code "130") (name "unconnected-(IC4-(PCINT5)PB5-Pad19)") (class "Default")
      (node (ref "IC4") (pin "19") (pinfunction "(PCINT5)PB5_19") (pintype "bidirectional"))
    )
    (net (code "131") (name "unconnected-(IC4-(PCINT6)PB6-Pad20)") (class "Default")
      (node (ref "IC4") (pin "20") (pinfunction "(PCINT6)PB6_20") (pintype "bidirectional"))
    )
    (net (code "132") (name "unconnected-(IC4-(PCINT7{slash}OC0A{slash}OC1C)PB7-Pad21)") (class "Default")
      (node (ref "IC4") (pin "21") (pinfunction "(PCINT7/OC0A/OC1C)PB7_21") (pintype "bidirectional"))
    )
    (net (code "133") (name "unconnected-(IC4-(PCINT9{slash}OC1B)PC5-Pad25)") (class "Default")
      (node (ref "IC4") (pin "25") (pinfunction "(PCINT9/OC1B)PC5_25") (pintype "bidirectional"))
    )
    (net (code "134") (name "unconnected-(IC4-(PCINT10)PC4-Pad26)") (class "Default")
      (node (ref "IC4") (pin "26") (pinfunction "(PCINT10)PC4_26") (pintype "bidirectional"))
    )
    (net (code "135") (name "unconnected-(IC4-(RTS{slash}AIN5{slash}INT6)PD6-Pad12)") (class "Default")
      (node (ref "IC4") (pin "12") (pinfunction "(RTS/AIN5/INT6)PD6_12") (pintype "bidirectional"))
    )
    (net (code "136") (name "unconnected-(IC4-(SS{slash}PCINT0)PB0-Pad14)") (class "Default")
      (node (ref "IC4") (pin "14") (pinfunction "(SS/PCINT0)PB0_14") (pintype "bidirectional"))
    )
    (net (code "137") (name "unconnected-(IC4-(T1{slash}PCINT4)PB4-Pad18)") (class "Default")
      (node (ref "IC4") (pin "18") (pinfunction "(T1/PCINT4)PB4_18") (pintype "bidirectional"))
    )
    (net (code "138") (name "unconnected-(IC5A-OUT-Pad1)") (class "Default")
      (node (ref "IC5") (pin "1") (pinfunction "OUT_1") (pintype "output"))
    )
    (net (code "139") (name "unconnected-(IC6-NC{slash}FB-Pad4)") (class "Default")
      (node (ref "IC6") (pin "4") (pinfunction "NC/FB_4") (pintype "passive"))
    )
    (net (code "140") (name "unconnected-(RN1D-1-Pad4)") (class "Default")
      (node (ref "RN1") (pin "4") (pinfunction "1_4") (pintype "passive"))
    )
    (net (code "141") (name "unconnected-(RN1D-2-Pad5)") (class "Default")
      (node (ref "RN1") (pin "5") (pinfunction "2_5") (pintype "passive"))
    )
    (net (code "142") (name "unconnected-(RN2B-1-Pad2)") (class "Default")
      (node (ref "RN2") (pin "2") (pinfunction "1_2") (pintype "passive"))
    )
    (net (code "143") (name "unconnected-(RN2B-2-Pad7)") (class "Default")
      (node (ref "RN2") (pin "7") (pinfunction "2_7") (pintype "passive"))
    )
    (net (code "144") (name "unconnected-(RN2C-1-Pad3)") (class "Default")
      (node (ref "RN2") (pin "3") (pinfunction "1_3") (pintype "passive"))
    )
    (net (code "145") (name "unconnected-(RN2C-2-Pad6)") (class "Default")
      (node (ref "RN2") (pin "6") (pinfunction "2_6") (pintype "passive"))
    )
    (net (code "146") (name "unconnected-(RN3-Pad1)") (class "Default")
      (node (ref "RN3") (pin "1") (pinfunction "1_1") (pintype "passive"))
    )
    (net (code "147") (name "unconnected-(RN3A-2-Pad8)") (class "Default")
      (node (ref "RN3") (pin "8") (pinfunction "2_8") (pintype "passive"))
    )
    (net (code "148") (name "unconnected-(RN3B-1-Pad2)") (class "Default")
      (node (ref "RN3") (pin "2") (pinfunction "1_2") (pintype "passive"))
    )
    (net (code "149") (name "unconnected-(RN3B-2-Pad7)") (class "Default")
      (node (ref "RN3") (pin "7") (pinfunction "2_7") (pintype "passive"))
    )
    (net (code "150") (name "unconnected-(RN5D-1-Pad4)") (class "Default")
      (node (ref "RN5") (pin "4") (pinfunction "1_4") (pintype "passive"))
    )
    (net (code "151") (name "unconnected-(RN5D-2-Pad5)") (class "Default")
      (node (ref "RN5") (pin "5") (pinfunction "2_5") (pintype "passive"))
    )
  )
)
